# NB679.net
KiCad netlist of a schematic drawn in Altium Designer
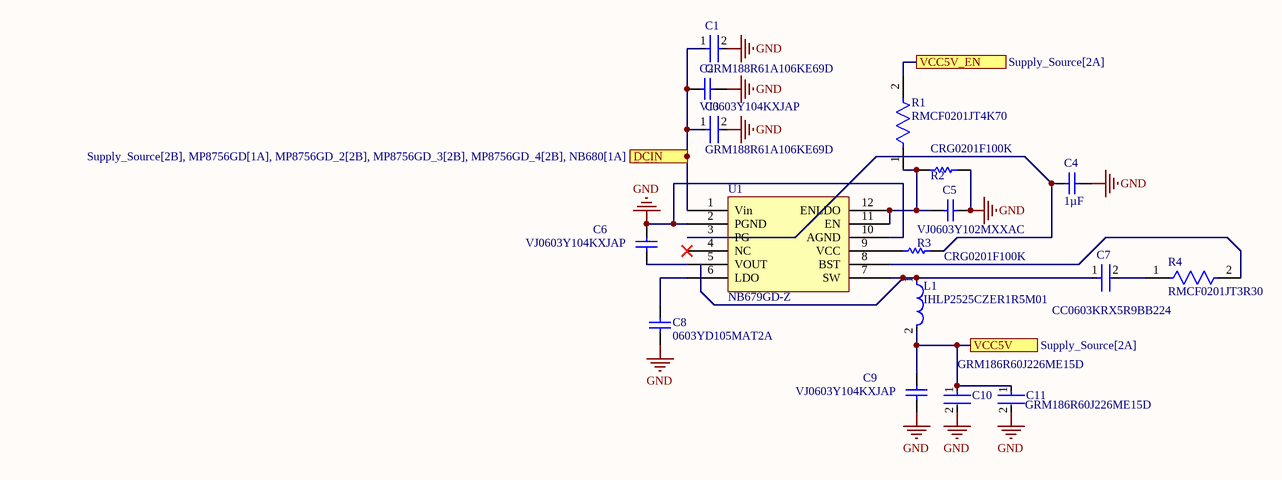
[diagram p0: NB679.SchDoc]

(export (version "E")
  (design (tool "Eeschema 10.0.6"))
  (components
    (comp (ref "C1")
      (value "GRM188R61A106KE69D")
      (footprint "FP-GRM18-0_15-MFG")
      (description "CAP CER 10UF 10V X5R 0603")
      (fields
        (field (name "OCTOPART") "https://octopart.com/grm188r61a106ke69d-murata-22851381")
        (field (name "MANUFACTURER") "Murata")
      )
      (libsource (lib "Altium Content Vault") (part "11868f565c42a9108669ba33697ecf6"))
    )
    (comp (ref "C2")
      (value "VJ0603Y104KXJAP")
      (footprint "CAPC1608X92X38NL15T08")
      (fields (field (name "MANUFACTURER") "Vitramon"))
      (libsource (lib "Altium Content Vault") (part "CAP"))
    )
    (comp (ref "C3")
      (value "GRM188R61A106KE69D")
      (footprint "FP-GRM18-0_15-MFG")
      (description "CAP CER 10UF 10V X5R 0603")
      (fields
        (field (name "OCTOPART") "https://octopart.com/grm188r61a106ke69d-murata-22851381")
        (field (name "MANUFACTURER") "Murata")
      )
      (libsource (lib "Altium Content Vault") (part "11868f565c42a9108669ba33697ecf6"))
    )
    (comp (ref "C4")
      (value "1µF")
      (footprint "CAPC1608X90X35LL15T15")
      (description "0603 1 uF 16 V ±20 % Tolerance X5R Surface Mount Multilayer Ceramic Capacitor")
      (fields (field (name "TOLERANCE") "20%") (field (name "Comment") "0603YD105MAT2A"))
      (libsource (lib "MIGUEL ANGEL ALVAREZ GUZMAN") (part "CAP"))
    )
    (comp (ref "C5")
      (value "VJ0603Y102MXXAC")
      (footprint "CAPC1608X92X38NL15T08")
      (fields (field (name "MANUFACTURER") "Vitramon"))
      (libsource (lib "Altium Content Vault") (part "CAP"))
    )
    (comp (ref "C6")
      (value "VJ0603Y104KXJAP")
      (footprint "CAPC1608X92X38NL15T08")
      (fields (field (name "MANUFACTURER") "Vitramon"))
      (libsource (lib "Altium Content Vault") (part "CAP"))
    )
    (comp (ref "C7")
      (value "CC0603KRX5R9BB224")
      (footprint "FP-CC0603-DA-MFG")
      (description "CC0603 220 nF X5R 10.00% 50 V")
      (fields
        (field (name "TOLERANCE") "0.1")
        (field (name "OCTOPART") "https://octopart.com/cc0603krx5r9bb224-yageo-90326743")
      )
      (libsource (lib "Altium Content Vault") (part "11868f565c42a9108669ba33697ecf6"))
    )
    (comp (ref "C8")
      (value "0603YD105MAT2A")
      (footprint "CAPC1608X90X35NL15T15")
      (fields (field (name "MANUFACTURER") "AVX Interconnect / Elco"))
      (libsource (lib "Altium Content Vault") (part "CAP"))
    )
    (comp (ref "C9")
      (value "VJ0603Y104KXJAP")
      (footprint "CAPC1608X92X38NL15T08")
      (fields (field (name "MANUFACTURER") "Vitramon"))
      (libsource (lib "Altium Content Vault") (part "CAP"))
    )
    (comp (ref "C10")
      (value "GRM186R60J226ME15D")
      (footprint "FP-GRM186-0_2-IPC_B")
      (description "Chip Multilayer Ceramic Capacitors for General Purpose, 0603, 22uF, X5R, 15%, 20%, 6.3V")
      (fields (field (name "TOLERANCE") "20%"))
      (libsource (lib "Altium Content Vault") (part "02cd4be3c70576c341d710602a673aa"))
    )
    (comp (ref "C11")
      (value "GRM186R60J226ME15D")
      (footprint "FP-GRM186-0_2-IPC_B")
      (description "Chip Multilayer Ceramic Capacitors for General Purpose, 0603, 22uF, X5R, 15%, 20%, 6.3V")
      (fields (field (name "TOLERANCE") "20%"))
      (libsource (lib "Altium Content Vault") (part "02cd4be3c70576c341d710602a673aa"))
    )
    (comp (ref "L1")
      (value "IHLP2525CZER1R5M01")
      (footprint "FP-IHLP-2525CZ-FP_2_413x3-MFG")
      (description "Commercial Inductors, High Saturation Series 1.5uH 9A 15mΩ 20%")
      (fields (field (name "TOLERANCE") "20%"))
      (libsource (lib "Altium Content Vault") (part "725321dda6339637d4d059423bc1c3c"))
    )
    (comp (ref "R1")
      (value "RMCF0201JT4K70")
      (footprint "FP-RMCF0201-IPC_C")
      (description "4.7kΩ ±5% 0.05W 0201 Thick Film Chip Resistor AEC-Q200 compliant")
      (fields (field (name "TOLERANCE") "5%"))
      (libsource (lib "Altium Content Vault") (part "1029c3af85768c4190bb7ad29bc67b5"))
    )
    (comp (ref "R2")
      (value "CRG0201F100K")
      (footprint "RESC0603X26X15LL03T05")
      (fields (field (name "MANUFACTURER") "TE Connectivity / AMP"))
      (libsource (lib "Altium Content Vault") (part "RES"))
    )
    (comp (ref "R3")
      (value "CRG0201F100K")
      (footprint "RESC0603X26X15LL03T05")
      (fields (field (name "MANUFACTURER") "TE Connectivity / AMP"))
      (libsource (lib "Altium Content Vault") (part "RES"))
    )
    (comp (ref "R4")
      (value "RMCF0201JT3R30")
      (footprint "FP-RMCF0201-IPC_A")
      (description "3.3Ω ±5% 0.05W 0201 Thick Film Chip Resistor AEC-Q200 compliant")
      (fields (field (name "TOLERANCE") "5%"))
      (libsource (lib "Altium Content Vault") (part "1029c3af85768c4190bb7ad29bc67b5"))
    )
    (comp (ref "U1")
      (value "NB679GD-Z")
      (footprint "NB679GD-Z-Footprint-1")
      (description "Step-Down (Buck) Synchronous (1), Linear (LDO) (1) QFN-12")
      (libsource (lib "MIGUEL ANGEL ALVAREZ GUZMAN") (part "NB679GD-Z-Symbol-1"))
    )
  )
  (nets
    (net (code "1") (name "/DCIN") (class "Default")
      (node (ref "C1") (pin "1") (pinfunction "1_1") (pintype "passive"))
      (node (ref "C2") (pin "2") (pinfunction "2_2") (pintype "passive"))
      (node (ref "C3") (pin "1") (pinfunction "1_1") (pintype "passive"))
      (node (ref "U1") (pin "1") (pinfunction "Vin_1") (pintype "passive"))
    )
    (net (code "2") (name "/VCC5V") (class "Default")
      (node (ref "C10") (pin "1") (pinfunction "1_1") (pintype "passive"))
      (node (ref "C11") (pin "1") (pinfunction "1_1") (pintype "passive"))
      (node (ref "C9") (pin "2") (pinfunction "2_2") (pintype "passive"))
      (node (ref "L1") (pin "2") (pinfunction "2_2") (pintype "passive"))
    )
    (net (code "3") (name "/VCC5V_EN") (class "Default")
      (node (ref "R1") (pin "2") (pinfunction "2_2") (pintype "passive"))
    )
    (net (code "4") (name "GND") (class "Default")
      (node (ref "C1") (pin "2") (pinfunction "2_2") (pintype "passive"))
      (node (ref "C10") (pin "2") (pinfunction "2_2") (pintype "passive"))
      (node (ref "C11") (pin "2") (pinfunction "2_2") (pintype "passive"))
      (node (ref "C2") (pin "1") (pinfunction "1_1") (pintype "passive"))
      (node (ref "C3") (pin "2") (pinfunction "2_2") (pintype "passive"))
      (node (ref "C4") (pin "1") (pinfunction "1_1") (pintype "passive"))
      (node (ref "C5") (pin "2") (pinfunction "2_2") (pintype "passive"))
      (node (ref "C6") (pin "2") (pinfunction "2_2") (pintype "passive"))
      (node (ref "C8") (pin "2") (pinfunction "2_2") (pintype "passive"))
      (node (ref "C9") (pin "1") (pinfunction "1_1") (pintype "passive"))
      (node (ref "R2") (pin "2") (pinfunction "2_2") (pintype "passive"))
      (node (ref "U1") (pin "10") (pinfunction "AGND_10") (pintype "passive"))
      (node (ref "U1") (pin "2") (pinfunction "PGND_2") (pintype "passive"))
    )
    (net (code "5") (name "Net-(C7-Pad2)") (class "Default")
      (node (ref "C7") (pin "2") (pinfunction "2_2") (pintype "passive"))
      (node (ref "R4") (pin "1") (pinfunction "1_1") (pintype "passive"))
    )
    (net (code "6") (name "Net-(U1-BST)") (class "Default")
      (node (ref "R4") (pin "2") (pinfunction "2_2") (pintype "passive"))
      (node (ref "U1") (pin "8") (pinfunction "BST_8") (pintype "passive"))
    )
    (net (code "7") (name "Net-(U1-EN)") (class "Default")
      (node (ref "C5") (pin "1") (pinfunction "1_1") (pintype "passive"))
      (node (ref "R1") (pin "1") (pinfunction "1_1") (pintype "passive"))
      (node (ref "R2") (pin "1") (pinfunction "1_1") (pintype "passive"))
      (node (ref "U1") (pin "11") (pinfunction "EN_11") (pintype "passive"))
      (node (ref "U1") (pin "12") (pinfunction "ENLDO_12") (pintype "passive"))
    )
    (net (code "8") (name "Net-(U1-LDO)") (class "Default")
      (node (ref "C8") (pin "1") (pinfunction "1_1") (pintype "passive"))
      (node (ref "U1") (pin "6") (pinfunction "LDO_6") (pintype "passive"))
    )
    (net (code "9") (name "Net-(U1-PG)") (class "Default")
      (node (ref "C4") (pin "2") (pinfunction "2_2") (pintype "passive"))
      (node (ref "R3") (pin "2") (pinfunction "2_2") (pintype "passive"))
      (node (ref "U1") (pin "3") (pinfunction "PG_3") (pintype "passive"))
    )
    (net (code "10") (name "Net-(U1-SW)") (class "Default")
      (node (ref "C7") (pin "1") (pinfunction "1_1") (pintype "passive"))
      (node (ref "L1") (pin "1") (pinfunction "1_1") (pintype "passive"))
      (node (ref "U1") (pin "7") (pinfunction "SW_7") (pintype "passive"))
    )
    (net (code "11") (name "Net-(U1-VCC)") (class "Default")
      (node (ref "R3") (pin "1") (pinfunction "1_1") (pintype "passive"))
      (node (ref "U1") (pin "9") (pinfunction "VCC_9") (pintype "passive"))
    )
    (net (code "12") (name "Net-(U1-VOUT)") (class "Default")
      (node (ref "C6") (pin "1") (pinfunction "1_1") (pintype "passive"))
      (node (ref "U1") (pin "5") (pinfunction "VOUT_5") (pintype "passive"))
    )
    (net (code "13") (name "unconnected-(U1-NC-Pad4)") (class "Default")
      (node (ref "U1") (pin "4") (pinfunction "NC_4") (pintype "passive+no_connect"))
    )
  )
)
